# Power_management.net
KiCad netlist of a schematic drawn in Altium Designer
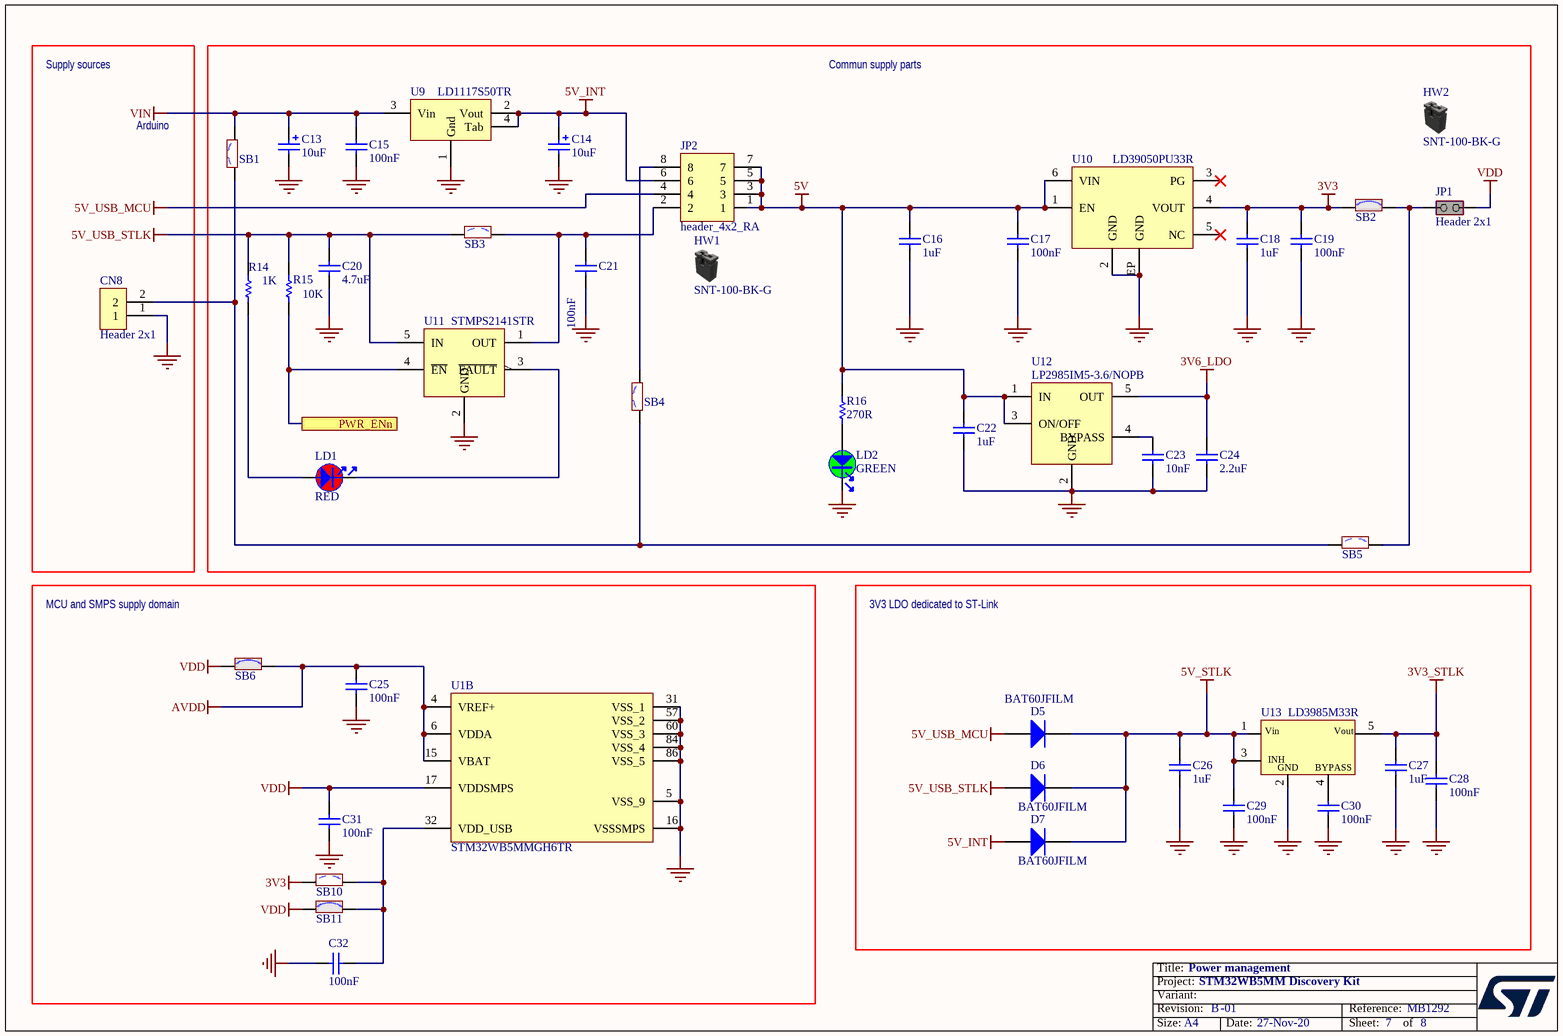
[diagram p0: Power_management.SchDoc]

(export (version "E")
  (design (tool "Eeschema 10.0.6"))
  (components
    (comp (ref "C13")
      (value "10uF")
      (footprint "CPOL_TAJ-B_1210_H210")
      (description "Capacitor, Tantalum, 10uF, 25V,2.5ohms, 10%, pkg Type_B (3528 metric), T=1.9mm")
      (fields
        (field (name "INTERNAL_PART_NUMBER") "MCD-00324")
        (field (name "MANUFACTURER_PART_NUMBER") "TAJB106K025RNJ")
      )
      (libsource (lib "MCD_PARTS_database") (part "Cap_POL_TANA"))
    )
    (comp (ref "C14")
      (value "10uF")
      (footprint "CPOL_TAJ-B_1210_H210")
      (description "Capacitor, Tantalum, 10uF, 25V,2.5ohms, 10%, pkg Type_B (3528 metric), T=1.9mm")
      (fields
        (field (name "INTERNAL_PART_NUMBER") "MCD-00324")
        (field (name "MANUFACTURER_PART_NUMBER") "TAJB106K025RNJ")
      )
      (libsource (lib "MCD_PARTS_database") (part "Cap_POL_TANA"))
    )
    (comp (ref "C15")
      (value "100nF")
      (footprint "C0805_H0P85")
      (description "Capacitor, MLCC, 100nF, 50V, X7R, 10%, 0805, T=0,85mm")
      (fields
        (field (name "INTERNAL_PART_NUMBER") "MCD-01525")
        (field (name "MANUFACTURER_PART_NUMBER") "CC0805KRX7R9BB104")
      )
      (libsource (lib "MCD_PARTS_database") (part "Capacitor"))
    )
    (comp (ref "C16")
      (value "1uF")
      (footprint "C0805_H0P85")
      (description "Capacitor, MLCC, 1uF, 16V, X5R, +/-10%, 0805, T=0.85mm")
      (fields
        (field (name "INTERNAL_PART_NUMBER") "MCD-01550")
        (field (name "MANUFACTURER_PART_NUMBER") "CC0805KRX5R7BB105")
      )
      (libsource (lib "MCD_PARTS_database") (part "Capacitor"))
    )
    (comp (ref "C17")
      (value "100nF")
      (footprint "C0201_H0P3")
      (description "Capacitor, MLCC,100nF, 10V, X7R, +/-10%, 0201, T=0.3mm")
      (fields
        (field (name "INTERNAL_PART_NUMBER") "MCD-01535")
        (field (name "MANUFACTURER_PART_NUMBER") "GRM033R61A104KE15")
      )
      (libsource (lib "MCD_PARTS_database") (part "Capacitor"))
    )
    (comp (ref "C18")
      (value "1uF")
      (footprint "C0805_H0P85")
      (description "Capacitor, MLCC, 1uF, 16V, X5R, +/-10%, 0805, T=0.85mm")
      (fields
        (field (name "INTERNAL_PART_NUMBER") "MCD-01550")
        (field (name "MANUFACTURER_PART_NUMBER") "CC0805KRX5R7BB105")
      )
      (libsource (lib "MCD_PARTS_database") (part "Capacitor"))
    )
    (comp (ref "C19")
      (value "100nF")
      (footprint "C0201_H0P3")
      (description "Capacitor, MLCC,100nF, 10V, X7R, +/-10%, 0201, T=0.3mm")
      (fields
        (field (name "INTERNAL_PART_NUMBER") "MCD-01535")
        (field (name "MANUFACTURER_PART_NUMBER") "GRM033R61A104KE15")
      )
      (libsource (lib "MCD_PARTS_database") (part "Capacitor"))
    )
    (comp (ref "C20")
      (value "4.7uF")
      (footprint "C0603_H0P8")
      (description "Capacitor, MLCC, 4.7uF, 10V, X5R, +/-10%, 0603, T=0.8mm")
      (fields
        (field (name "INTERNAL_PART_NUMBER") "MCD-01721")
        (field (name "MANUFACTURER_PART_NUMBER") "CC0603KRX5R6BB475")
      )
      (libsource (lib "MCD_PARTS_database") (part "Capacitor"))
    )
    (comp (ref "C21")
      (value "100nF")
      (footprint "C0805_H0P85")
      (description "Capacitor, MLCC, 100nF, 50V, X7R, 10%, 0805, T=0,85mm")
      (fields
        (field (name "INTERNAL_PART_NUMBER") "MCD-01525")
        (field (name "MANUFACTURER_PART_NUMBER") "CC0805KRX7R9BB104")
      )
      (libsource (lib "MCD_PARTS_database") (part "Capacitor"))
    )
    (comp (ref "C22")
      (value "1uF")
      (footprint "C0603")
      (description "Capacitor, MLCC, 1uF, 16V, X5R, +/-10%, 0603, T=0,8mm")
      (fields
        (field (name "INTERNAL_PART_NUMBER") "MCD-00010")
        (field (name "MANUFACTURER_PART_NUMBER") "CC0603KRX5R7BB105")
      )
      (libsource (lib "MCD_PARTS_database") (part "Capacitor"))
    )
    (comp (ref "C23")
      (value "10nF")
      (footprint "C0603")
      (description "Capacitor, MLCC, 10nF, 16V, X7R, +/-10%, 0603, T=0.8mm")
      (fields
        (field (name "INTERNAL_PART_NUMBER") "MCD-01007")
        (field (name "MANUFACTURER_PART_NUMBER") "CC0603KRX7R7BB103")
      )
      (libsource (lib "MCD_PARTS_database") (part "Capacitor"))
    )
    (comp (ref "C24")
      (value "2.2uF")
      (footprint "C0603")
      (description "Capacitor, MLCC, 2.2uF, 10V, X5R, +/- 10%, 0603, T=0,8mm")
      (fields
        (field (name "INTERNAL_PART_NUMBER") "MCD-00012")
        (field (name "MANUFACTURER_PART_NUMBER") "CC0603KRX5R6BB225")
      )
      (libsource (lib "MCD_PARTS_database") (part "Capacitor"))
    )
    (comp (ref "C25")
      (value "100nF")
      (footprint "C0201_H0P3")
      (description "Capacitor, MLCC,100nF, 10V, X7R, +/-10%, 0201, T=0.3mm")
      (fields
        (field (name "INTERNAL_PART_NUMBER") "MCD-01535")
        (field (name "MANUFACTURER_PART_NUMBER") "GRM033R61A104KE15")
      )
      (libsource (lib "MCD_PARTS_database") (part "Capacitor"))
    )
    (comp (ref "C26")
      (value "1uF")
      (footprint "C0402")
      (description "Capacitor, MLCC, 1uF, 10V, X5R, +/-10%, 0402, T=0.5mm")
      (fields
        (field (name "INTERNAL_PART_NUMBER") "MCD-01722")
        (field (name "MANUFACTURER_PART_NUMBER") "CC0402KRX5R6BB105")
      )
      (libsource (lib "MCD_PARTS_database") (part "Capacitor"))
    )
    (comp (ref "C27")
      (value "1uF")
      (footprint "C0402")
      (description "Capacitor, MLCC, 1uF, 10V, X5R, +/-10%, 0402, T=0.5mm")
      (fields
        (field (name "INTERNAL_PART_NUMBER") "MCD-01722")
        (field (name "MANUFACTURER_PART_NUMBER") "CC0402KRX5R6BB105")
      )
      (libsource (lib "MCD_PARTS_database") (part "Capacitor"))
    )
    (comp (ref "C28")
      (value "100nF")
      (footprint "C0201_H0P3")
      (description "Capacitor, MLCC,100nF, 10V, X7R, +/-10%, 0201, T=0.3mm")
      (fields
        (field (name "INTERNAL_PART_NUMBER") "MCD-01535")
        (field (name "MANUFACTURER_PART_NUMBER") "GRM033R61A104KE15")
      )
      (libsource (lib "MCD_PARTS_database") (part "Capacitor"))
    )
    (comp (ref "C29")
      (value "100nF")
      (footprint "C0201_H0P3")
      (description "Capacitor, MLCC,100nF, 10V, X7R, +/-10%, 0201, T=0.3mm")
      (fields
        (field (name "INTERNAL_PART_NUMBER") "MCD-01535")
        (field (name "MANUFACTURER_PART_NUMBER") "GRM033R61A104KE15")
      )
      (libsource (lib "MCD_PARTS_database") (part "Capacitor"))
    )
    (comp (ref "C30")
      (value "100nF")
      (footprint "C0201_H0P3")
      (description "Capacitor, MLCC,100nF, 10V, X7R, +/-10%, 0201, T=0.3mm")
      (fields
        (field (name "INTERNAL_PART_NUMBER") "MCD-01535")
        (field (name "MANUFACTURER_PART_NUMBER") "GRM033R61A104KE15")
      )
      (libsource (lib "MCD_PARTS_database") (part "Capacitor"))
    )
    (comp (ref "C31")
      (value "100nF")
      (footprint "C0201_H0P3")
      (description "Capacitor, MLCC,100nF, 10V, X7R, +/-10%, 0201, T=0.3mm")
      (fields
        (field (name "INTERNAL_PART_NUMBER") "MCD-01535")
        (field (name "MANUFACTURER_PART_NUMBER") "GRM033R61A104KE15")
      )
      (libsource (lib "MCD_PARTS_database") (part "Capacitor"))
    )
    (comp (ref "C32")
      (value "100nF")
      (footprint "C0201_H0P3")
      (description "Capacitor, MLCC,100nF, 10V, X7R, +/-10%, 0201, T=0.3mm")
      (fields
        (field (name "INTERNAL_PART_NUMBER") "MCD-01535")
        (field (name "MANUFACTURER_PART_NUMBER") "GRM033R61A104KE15")
      )
      (libsource (lib "MCD_PARTS_database") (part "Capacitor"))
    )
    (comp (ref "CN8")
      (value "Header 2x1")
      (footprint "CON_LYCONN_313102S141346")
      (description "Header 2x1, 2.54mm, VR, TH, height 5.84mm/5.08 mm, height total 13.46 mm")
      (fields
        (field (name "INTERNAL_PART_NUMBER") "MCD-01668")
        (field (name "MANUFACTURER_PART_NUMBER") "313102S141346")
      )
      (libsource (lib "MCD_PARTS_database") (part "Header 2x1"))
    )
    (comp (ref "D5")
      (value "BAT60JFILM")
      (footprint "DIO_SOD323")
      (fields
        (field (name "INTERNAL_PART_NUMBER") "MCD-00034")
        (field (name "MANUFACTURER") "STMICROELECTRONICS")
        (field (name "BMS_PART_NUMBER") "9151097")
      )
      (libsource (lib "MCD_PARTS_database") (part "BAT60JFILM"))
    )
    (comp (ref "D6")
      (value "BAT60JFILM")
      (footprint "DIO_SOD323")
      (fields
        (field (name "INTERNAL_PART_NUMBER") "MCD-00034")
        (field (name "MANUFACTURER") "STMICROELECTRONICS")
        (field (name "BMS_PART_NUMBER") "9151097")
      )
      (libsource (lib "MCD_PARTS_database") (part "BAT60JFILM"))
    )
    (comp (ref "D7")
      (value "BAT60JFILM")
      (footprint "DIO_SOD323")
      (fields
        (field (name "INTERNAL_PART_NUMBER") "MCD-00034")
        (field (name "MANUFACTURER") "STMICROELECTRONICS")
        (field (name "BMS_PART_NUMBER") "9151097")
      )
      (libsource (lib "MCD_PARTS_database") (part "BAT60JFILM"))
    )
    (comp (ref "HW1")
      (value "SNT-100-BK-G")
      (description "SHUNT 2.54mm BLACK")
      (fields (field (name "INTERNAL_PART_NUMBER") "MCD-00043") (field (name "MANUFACTURER") "SAMTEC"))
      (libsource (lib "MCD_PARTS_database") (part "Shunt Black 2.54mm"))
    )
    (comp (ref "HW2")
      (value "SNT-100-BK-G")
      (description "SHUNT 2.54mm BLACK")
      (fields (field (name "INTERNAL_PART_NUMBER") "MCD-00043") (field (name "MANUFACTURER") "SAMTEC"))
      (libsource (lib "MCD_PARTS_database") (part "Shunt Black 2.54mm"))
    )
    (comp (ref "JP1")
      (value "Header 2x1")
      (footprint "CON_SAMTEC_TSW-102-07-G-S")
      (description "Header, 2x1, 2,54mm, VR, TH, Height 5.84mm/2.54mm - Shunt Fitted by default")
      (fields
        (field (name "INTERNAL_PART_NUMBER") "MCD-01904")
        (field (name "MANUFACTURER_PART_NUMBER") "TSW-102-07-G-S")
      )
      (libsource (lib "MCD_PARTS_database") (part "Jumper_Header 2x1 Fitted"))
    )
    (comp (ref "JP2")
      (value "header_4x2_RA")
      (footprint "CON_SAMTEC_TSW-104-08-F-D-RA")
      (description "Header, 4x2, 2,29mm, RA, TH, height 5,84mm")
      (fields
        (field (name "INTERNAL_PART_NUMBER") "MCD-02037")
        (field (name "MANUFACTURER_PART_NUMBER") "TSW-104-08-F-D-RA")
      )
      (libsource (lib "MCD_PARTS_database") (part "Header 4x2"))
    )
    (comp (ref "LD1")
      (value "RED")
      (footprint "LED_0603_RED_H0P4")
      (description "LED, Red, 0603")
      (fields
        (field (name "INTERNAL_PART_NUMBER") "MCD-00322")
        (field (name "MANUFACTURER_PART_NUMBER") "19-217/R6C-AL1M2VY/3T")
      )
      (libsource (lib "MCD_PARTS_database") (part "LED_red"))
    )
    (comp (ref "LD2")
      (value "GREEN")
      (footprint "LED_0603_OSRAM_LG-Q396-PS-35_GREEN_1A2K_H0P4")
      (description "LED Green, 0603 SMD, Forward Voltage Typ=2V, Max=2.5V")
      (fields
        (field (name "INTERNAL_PART_NUMBER") "MCD-00588")
        (field (name "MANUFACTURER_PART_NUMBER") "LG Q396-PS-35")
      )
      (libsource (lib "MCD_PARTS_database") (part "LED_green"))
    )
    (comp (ref "R14")
      (value "1K")
      (footprint "R0603")
      (description "Resistor,1K,0603,1%,1/10W")
      (fields
        (field (name "INTERNAL_PART_NUMBER") "MCD-00070")
        (field (name "MANUFACTURER_PART_NUMBER") "RC0603FR-071KL")
      )
      (libsource (lib "MCD_PARTS_database") (part "Resistor"))
    )
    (comp (ref "R15")
      (value "10K")
      (footprint "R0603")
      (description "Resistor,10K,0603,1%,1/10W")
      (fields
        (field (name "INTERNAL_PART_NUMBER") "MCD-00220")
        (field (name "MANUFACTURER_PART_NUMBER") "RC0603FR-0710KL")
      )
      (libsource (lib "MCD_PARTS_database") (part "Resistor"))
    )
    (comp (ref "R16")
      (value "270R")
      (footprint "R0603")
      (description "Resistor,270R,0603,1%,1/10W")
      (fields
        (field (name "INTERNAL_PART_NUMBER") "MCD-00442")
        (field (name "MANUFACTURER_PART_NUMBER") "RC0603FR-07270RL")
      )
      (libsource (lib "MCD_PARTS_database") (part "Resistor"))
    )
    (comp (ref "SB1")
      (value "SB_OFF")
      (footprint "SOLDER-BRIDGE_R0603-0R")
      (description "Solder Bridge OFF")
      (fields
        (field (name "INTERNAL_PART_NUMBER") "MCD-00072")
        (field (name "MANUFACTURER_PART_NUMBER") "RC0603JR-070RL")
      )
      (libsource (lib "MCD_PARTS_database") (part "SB_OFF"))
    )
    (comp (ref "SB2")
      (value "SB_ON")
      (footprint "SOLDER-BRIDGE_R0603-0R")
      (description "Solder Bridge ON")
      (fields
        (field (name "INTERNAL_PART_NUMBER") "MCD-00071")
        (field (name "MANUFACTURER_PART_NUMBER") "RC0603JR-070RL")
      )
      (libsource (lib "MCD_PARTS_database") (part "SB_ON"))
    )
    (comp (ref "SB3")
      (value "SB_OFF")
      (footprint "SOLDER-BRIDGE_R0603-0R")
      (description "Solder Bridge OFF")
      (fields
        (field (name "INTERNAL_PART_NUMBER") "MCD-00072")
        (field (name "MANUFACTURER_PART_NUMBER") "RC0603JR-070RL")
      )
      (libsource (lib "") (part "SB_OFF_1"))
    )
    (comp (ref "SB4")
      (value "SB_OFF")
      (footprint "SOLDER-BRIDGE_R0603-0R")
      (description "Solder Bridge OFF")
      (fields
        (field (name "INTERNAL_PART_NUMBER") "MCD-00072")
        (field (name "MANUFACTURER_PART_NUMBER") "RC0603JR-070RL")
      )
      (libsource (lib "MCD_PARTS_database") (part "SB_OFF"))
    )
    (comp (ref "SB5")
      (value "SB_OFF")
      (footprint "SOLDER-BRIDGE_R0603-0R")
      (description "Solder Bridge OFF")
      (fields
        (field (name "INTERNAL_PART_NUMBER") "MCD-00072")
        (field (name "MANUFACTURER_PART_NUMBER") "RC0603JR-070RL")
      )
      (libsource (lib "") (part "SB_OFF_1"))
    )
    (comp (ref "SB6")
      (value "SB_ON")
      (footprint "SOLDER-BRIDGE_R0603-0R")
      (description "Solder Bridge ON")
      (fields
        (field (name "INTERNAL_PART_NUMBER") "MCD-00071")
        (field (name "MANUFACTURER_PART_NUMBER") "RC0603JR-070RL")
      )
      (libsource (lib "MCD_PARTS_database") (part "SB_ON"))
    )
    (comp (ref "SB10")
      (value "SB_OFF")
      (footprint "SOLDER-BRIDGE_R0603-0R")
      (description "Solder Bridge OFF")
      (fields
        (field (name "INTERNAL_PART_NUMBER") "MCD-00072")
        (field (name "MANUFACTURER_PART_NUMBER") "RC0603JR-070RL")
      )
      (libsource (lib "") (part "SB_OFF_1"))
    )
    (comp (ref "SB11")
      (value "SB_ON")
      (footprint "SOLDER-BRIDGE_R0603-0R")
      (description "Solder Bridge ON")
      (fields
        (field (name "INTERNAL_PART_NUMBER") "MCD-00071")
        (field (name "MANUFACTURER_PART_NUMBER") "RC0603JR-070RL")
      )
      (libsource (lib "MCD_PARTS_database") (part "SB_ON"))
    )
    (comp (ref "U1")
      (value "STM32WB5MMGH6TR")
      (footprint "MOD_DORY_STM_86P_7P3X11_H1P342")
      (description "STM32 BLE module based on STM32WB55")
      (fields
        (field (name "INTERNAL_PART_NUMBER") "MCD-01965")
        (field (name "MANUFACTURER") "STMICROELECTRONICS")
      )
      (libsource (lib "MCD_PARTS_database") (part "STM32WB5MMGH6TR"))
    )
    (comp (ref "U9")
      (value "LD1117S50TR")
      (footprint "REG_SOT223-TAB")
      (description "IC REG LDO 5V 0.8A SOT223")
      (fields
        (field (name "INTERNAL_PART_NUMBER") "MCD-00088")
        (field (name "MANUFACTURER") "STMICROELECTRONICS")
      )
      (libsource (lib "MCD_PARTS_database") (part "LD1117S50TR"))
    )
    (comp (ref "U10")
      (value "LD39050PU33R")
      (footprint "ICC_DFN6-EPAD_3X3_P095")
      (description "Low quiescent current and low noise voltage regulators")
      (fields
        (field (name "INTERNAL_PART_NUMBER") "MCD-00215")
        (field (name "MANUFACTURER") "STMICROELECTRONICS")
      )
      (libsource (lib "MCD_PARTS_database") (part "LD39050PU33R"))
    )
    (comp (ref "U11")
      (value "STMPS2141STR")
      (footprint "MOS_SOT23-5L")
      (description "Enhanced single channel power switches with active low enable pin")
      (fields
        (field (name "INTERNAL_PART_NUMBER") "MCD-00083")
        (field (name "MANUFACTURER") "STMICROELECTRONICS")
      )
      (libsource (lib "MCD_PARTS_database") (part "STMPS2141STR"))
    )
    (comp (ref "U12")
      (value "LP2985IM5-3.6/NOPB")
      (footprint "REG_SOT23-5L")
      (description "LDO VOLTAGE REGULATOR, 3.6V, 150mA, 5-SOT-23, FULL REEL")
      (fields
        (field (name "INTERNAL_PART_NUMBER") "MCD-01030")
        (field (name "MANUFACTURER") "TEXAS INSTRUMENTS")
      )
      (libsource (lib "MCD_PARTS_database") (part "LP2985IM5-3.6/NOPB"))
    )
    (comp (ref "U13")
      (value "LD3985M33R")
      (footprint "REG_SOT23-5L")
      (description "Ultra low drop-low noise BiCMOS voltage, regulators low ESR capacitors compatible")
      (fields
        (field (name "INTERNAL_PART_NUMBER") "MCD-00086")
        (field (name "MANUFACTURER") "STMICROELECTRONICS")
      )
      (libsource (lib "MCD_PARTS_database") (part "LD3985M33R"))
    )
  )
  (nets
    (net (code "1") (name "/PWR_ENn") (class "Default")
      (node (ref "R15") (pin "1") (pinfunction "1_1") (pintype "passive"))
      (node (ref "U11") (pin "4") (pinfunction "~{EN}_4") (pintype "passive"))
    )
    (net (code "2") (name "3V3") (class "Default")
      (node (ref "C18") (pin "2") (pinfunction "2_2") (pintype "passive"))
      (node (ref "C19") (pin "2") (pinfunction "2_2") (pintype "passive"))
      (node (ref "SB10") (pin "1") (pinfunction "1_1") (pintype "passive"))
      (node (ref "SB2") (pin "1") (pinfunction "1_1") (pintype "passive"))
      (node (ref "U10") (pin "4") (pinfunction "VOUT_4") (pintype "passive"))
    )
    (net (code "3") (name "3V3_STLK") (class "Default")
      (node (ref "C27") (pin "2") (pinfunction "2_2") (pintype "passive"))
      (node (ref "C28") (pin "2") (pinfunction "2_2") (pintype "passive"))
      (node (ref "U13") (pin "5") (pinfunction "Vout_5") (pintype "passive"))
    )
    (net (code "4") (name "3V6_LDO") (class "Default")
      (node (ref "C24") (pin "2") (pinfunction "2_2") (pintype "passive"))
      (node (ref "U12") (pin "5") (pinfunction "OUT_5") (pintype "passive"))
    )
    (net (code "5") (name "5V") (class "Default")
      (node (ref "C16") (pin "2") (pinfunction "2_2") (pintype "passive"))
      (node (ref "C17") (pin "2") (pinfunction "2_2") (pintype "passive"))
      (node (ref "C22") (pin "1") (pinfunction "1_1") (pintype "passive"))
      (node (ref "JP2") (pin "1") (pinfunction "1_1") (pintype "passive"))
      (node (ref "JP2") (pin "3") (pinfunction "3_3") (pintype "passive"))
      (node (ref "JP2") (pin "5") (pinfunction "5_5") (pintype "passive"))
      (node (ref "JP2") (pin "7") (pinfunction "7_7") (pintype "passive"))
      (node (ref "R16") (pin "2") (pinfunction "2_2") (pintype "passive"))
      (node (ref "U10") (pin "1") (pinfunction "EN_1") (pintype "passive"))
      (node (ref "U10") (pin "6") (pinfunction "VIN_6") (pintype "passive"))
      (node (ref "U12") (pin "1") (pinfunction "IN_1") (pintype "passive"))
      (node (ref "U12") (pin "3") (pinfunction "ON/OFF_3") (pintype "passive"))
    )
    (net (code "6") (name "5V_INT") (class "Default")
      (node (ref "C14") (pin "1") (pinfunction "1_1") (pintype "passive"))
      (node (ref "D7") (pin "1") (pinfunction "A_1") (pintype "passive"))
      (node (ref "JP2") (pin "6") (pinfunction "6_6") (pintype "passive"))
      (node (ref "U9") (pin "2") (pinfunction "Vout_2") (pintype "passive"))
      (node (ref "U9") (pin "4") (pinfunction "Tab_4") (pintype "passive"))
    )
    (net (code "7") (name "5V_STLK") (class "Default")
      (node (ref "C26") (pin "2") (pinfunction "2_2") (pintype "passive"))
      (node (ref "C29") (pin "2") (pinfunction "2_2") (pintype "passive"))
      (node (ref "D5") (pin "2") (pinfunction "K_2") (pintype "passive"))
      (node (ref "D6") (pin "2") (pinfunction "K_2") (pintype "passive"))
      (node (ref "D7") (pin "2") (pinfunction "K_2") (pintype "passive"))
      (node (ref "U13") (pin "1") (pinfunction "Vin_1") (pintype "passive"))
      (node (ref "U13") (pin "3") (pinfunction "CE_3") (pintype "passive"))
    )
    (net (code "8") (name "5V_USB_MCU") (class "Default")
      (node (ref "D5") (pin "1") (pinfunction "A_1") (pintype "passive"))
      (node (ref "JP2") (pin "4") (pinfunction "4_4") (pintype "passive"))
    )
    (net (code "9") (name "5V_USB_STLK") (class "Default")
      (node (ref "C20") (pin "2") (pinfunction "2_2") (pintype "passive"))
      (node (ref "D6") (pin "1") (pinfunction "A_1") (pintype "passive"))
      (node (ref "R14") (pin "2") (pinfunction "2_2") (pintype "passive"))
      (node (ref "R15") (pin "2") (pinfunction "2_2") (pintype "passive"))
      (node (ref "SB3") (pin "1") (pinfunction "1_1") (pintype "passive"))
      (node (ref "U11") (pin "5") (pinfunction "IN_5") (pintype "passive"))
    )
    (net (code "10") (name "AVDD") (class "Default")
      (node (ref "C25") (pin "2") (pinfunction "2_2") (pintype "passive"))
      (node (ref "SB6") (pin "2") (pinfunction "2_2") (pintype "passive"))
      (node (ref "U1") (pin "15") (pinfunction "VBAT_15") (pintype "passive"))
      (node (ref "U1") (pin "4") (pinfunction "VREF+_4") (pintype "passive"))
      (node (ref "U1") (pin "6") (pinfunction "VDDA_6") (pintype "passive"))
    )
    (net (code "11") (name "GND") (class "Default")
      (node (ref "C13") (pin "2") (pinfunction "2_2") (pintype "passive"))
      (node (ref "C14") (pin "2") (pinfunction "2_2") (pintype "passive"))
      (node (ref "C15") (pin "1") (pinfunction "1_1") (pintype "passive"))
      (node (ref "C16") (pin "1") (pinfunction "1_1") (pintype "passive"))
      (node (ref "C17") (pin "1") (pinfunction "1_1") (pintype "passive"))
      (node (ref "C18") (pin "1") (pinfunction "1_1") (pintype "passive"))
      (node (ref "C19") (pin "1") (pinfunction "1_1") (pintype "passive"))
      (node (ref "C20") (pin "1") (pinfunction "1_1") (pintype "passive"))
      (node (ref "C21") (pin "1") (pinfunction "1_1") (pintype "passive"))
      (node (ref "C22") (pin "2") (pinfunction "2_2") (pintype "passive"))
      (node (ref "C23") (pin "1") (pinfunction "1_1") (pintype "passive"))
      (node (ref "C24") (pin "1") (pinfunction "1_1") (pintype "passive"))
      (node (ref "C25") (pin "1") (pinfunction "1_1") (pintype "passive"))
      (node (ref "C26") (pin "1") (pinfunction "1_1") (pintype "passive"))
      (node (ref "C27") (pin "1") (pinfunction "1_1") (pintype "passive"))
      (node (ref "C28") (pin "1") (pinfunction "1_1") (pintype "passive"))
      (node (ref "C29") (pin "1") (pinfunction "1_1") (pintype "passive"))
      (node (ref "C30") (pin "1") (pinfunction "1_1") (pintype "passive"))
      (node (ref "C31") (pin "1") (pinfunction "1_1") (pintype "passive"))
      (node (ref "C32") (pin "2") (pinfunction "2_2") (pintype "passive"))
      (node (ref "CN8") (pin "1") (pinfunction "1_1") (pintype "passive"))
      (node (ref "LD2") (pin "2") (pintype "passive"))
      (node (ref "U1") (pin "16") (pinfunction "VSSSMPS_16") (pintype "passive"))
      (node (ref "U1") (pin "31") (pinfunction "VSS_1_31") (pintype "passive"))
      (node (ref "U1") (pin "5") (pinfunction "VSS_9_5") (pintype "passive"))
      (node (ref "U1") (pin "57") (pinfunction "VSS_2_57") (pintype "passive"))
      (node (ref "U1") (pin "60") (pinfunction "VSS_3_60") (pintype "passive"))
      (node (ref "U1") (pin "84") (pinfunction "VSS_4_84") (pintype "passive"))
      (node (ref "U1") (pin "86") (pinfunction "VSS_5_86") (pintype "passive"))
      (node (ref "U10") (pin "2") (pinfunction "GND_2") (pintype "passive"))
      (node (ref "U10") (pin "EP") (pinfunction "GND_EP") (pintype "passive"))
      (node (ref "U11") (pin "2") (pinfunction "GND_2") (pintype "passive"))
      (node (ref "U12") (pin "2") (pinfunction "GND_2") (pintype "passive"))
      (node (ref "U13") (pin "2") (pinfunction "GND_2") (pintype "passive"))
      (node (ref "U9") (pin "1") (pinfunction "Gnd_1") (pintype "passive"))
    )
    (net (code "12") (name "Net-(CN8-Pad2)") (class "Default")
      (node (ref "CN8") (pin "2") (pinfunction "2_2") (pintype "passive"))
      (node (ref "SB1") (pin "1") (pinfunction "1_1") (pintype "passive"))
      (node (ref "SB4") (pin "1") (pinfunction "1_1") (pintype "passive"))
      (node (ref "SB5") (pin "1") (pinfunction "1_1") (pintype "passive"))
    )
    (net (code "13") (name "Net-(JP1-COMMON)") (class "Default")
      (node (ref "JP1") (pin "1") (pinfunction "COMMON_1") (pintype "passive"))
      (node (ref "SB2") (pin "2") (pinfunction "2_2") (pintype "passive"))
      (node (ref "SB5") (pin "2") (pinfunction "2_2") (pintype "passive"))
    )
    (net (code "14") (name "Net-(JP2-Pad8)") (class "Default")
      (node (ref "JP2") (pin "8") (pinfunction "8_8") (pintype "passive"))
      (node (ref "SB4") (pin "2") (pinfunction "2_2") (pintype "passive"))
    )
    (net (code "15") (name "Net-(LD1-Pad1)") (class "Default")
      (node (ref "LD1") (pin "1") (pintype "passive"))
      (node (ref "R14") (pin "1") (pinfunction "1_1") (pintype "passive"))
    )
    (net (code "16") (name "Net-(LD2-Pad1)") (class "Default")
      (node (ref "LD2") (pin "1") (pintype "passive"))
      (node (ref "R16") (pin "1") (pinfunction "1_1") (pintype "passive"))
    )
    (net (code "17") (name "Net-(U1B-VDD_USB)") (class "Default")
      (node (ref "C32") (pin "1") (pinfunction "1_1") (pintype "passive"))
      (node (ref "SB10") (pin "2") (pinfunction "2_2") (pintype "passive"))
      (node (ref "SB11") (pin "2") (pinfunction "2_2") (pintype "passive"))
      (node (ref "U1") (pin "32") (pinfunction "VDD_USB_32") (pintype "passive"))
    )
    (net (code "18") (name "Net-(U11-OUT)") (class "Default")
      (node (ref "C21") (pin "2") (pinfunction "2_2") (pintype "passive"))
      (node (ref "JP2") (pin "2") (pinfunction "2_2") (pintype "passive"))
      (node (ref "SB3") (pin "2") (pinfunction "2_2") (pintype "passive"))
      (node (ref "U11") (pin "1") (pinfunction "OUT_1") (pintype "passive"))
    )
    (net (code "19") (name "Net-(U11-~{FAULT})") (class "Default")
      (node (ref "LD1") (pin "2") (pintype "passive"))
      (node (ref "U11") (pin "3") (pinfunction "~{FAULT}_3") (pintype "passive"))
    )
    (net (code "20") (name "Net-(U12-BYPASS)") (class "Default")
      (node (ref "C23") (pin "2") (pinfunction "2_2") (pintype "passive"))
      (node (ref "U12") (pin "4") (pinfunction "BYPASS_4") (pintype "passive"))
    )
    (net (code "21") (name "Net-(U13-BYPASS)") (class "Default")
      (node (ref "C30") (pin "2") (pinfunction "2_2") (pintype "passive"))
      (node (ref "U13") (pin "4") (pinfunction "BYPASS_4") (pintype "passive"))
    )
    (net (code "22") (name "VDD") (class "Default")
      (node (ref "C31") (pin "2") (pinfunction "2_2") (pintype "passive"))
      (node (ref "JP1") (pin "2") (pinfunction "NO_2") (pintype "passive"))
      (node (ref "SB11") (pin "1") (pinfunction "1_1") (pintype "passive"))
      (node (ref "SB6") (pin "1") (pinfunction "1_1") (pintype "passive"))
      (node (ref "U1") (pin "17") (pinfunction "VDDSMPS_17") (pintype "passive"))
    )
    (net (code "23") (name "VIN") (class "Default")
      (node (ref "C13") (pin "1") (pinfunction "1_1") (pintype "passive"))
      (node (ref "C15") (pin "2") (pinfunction "2_2") (pintype "passive"))
      (node (ref "SB1") (pin "2") (pinfunction "2_2") (pintype "passive"))
      (node (ref "U9") (pin "3") (pinfunction "Vin_3") (pintype "passive"))
    )
    (net (code "24") (name "unconnected-(U10-NC-Pad5)") (class "Default")
      (node (ref "U10") (pin "5") (pinfunction "NC_5") (pintype "passive+no_connect"))
    )
    (net (code "25") (name "unconnected-(U10-PG-Pad3)") (class "Default")
      (node (ref "U10") (pin "3") (pinfunction "PG_3") (pintype "passive+no_connect"))
    )
  )
)
